# NVME.net
KiCad netlist of a schematic drawn in Altium Designer
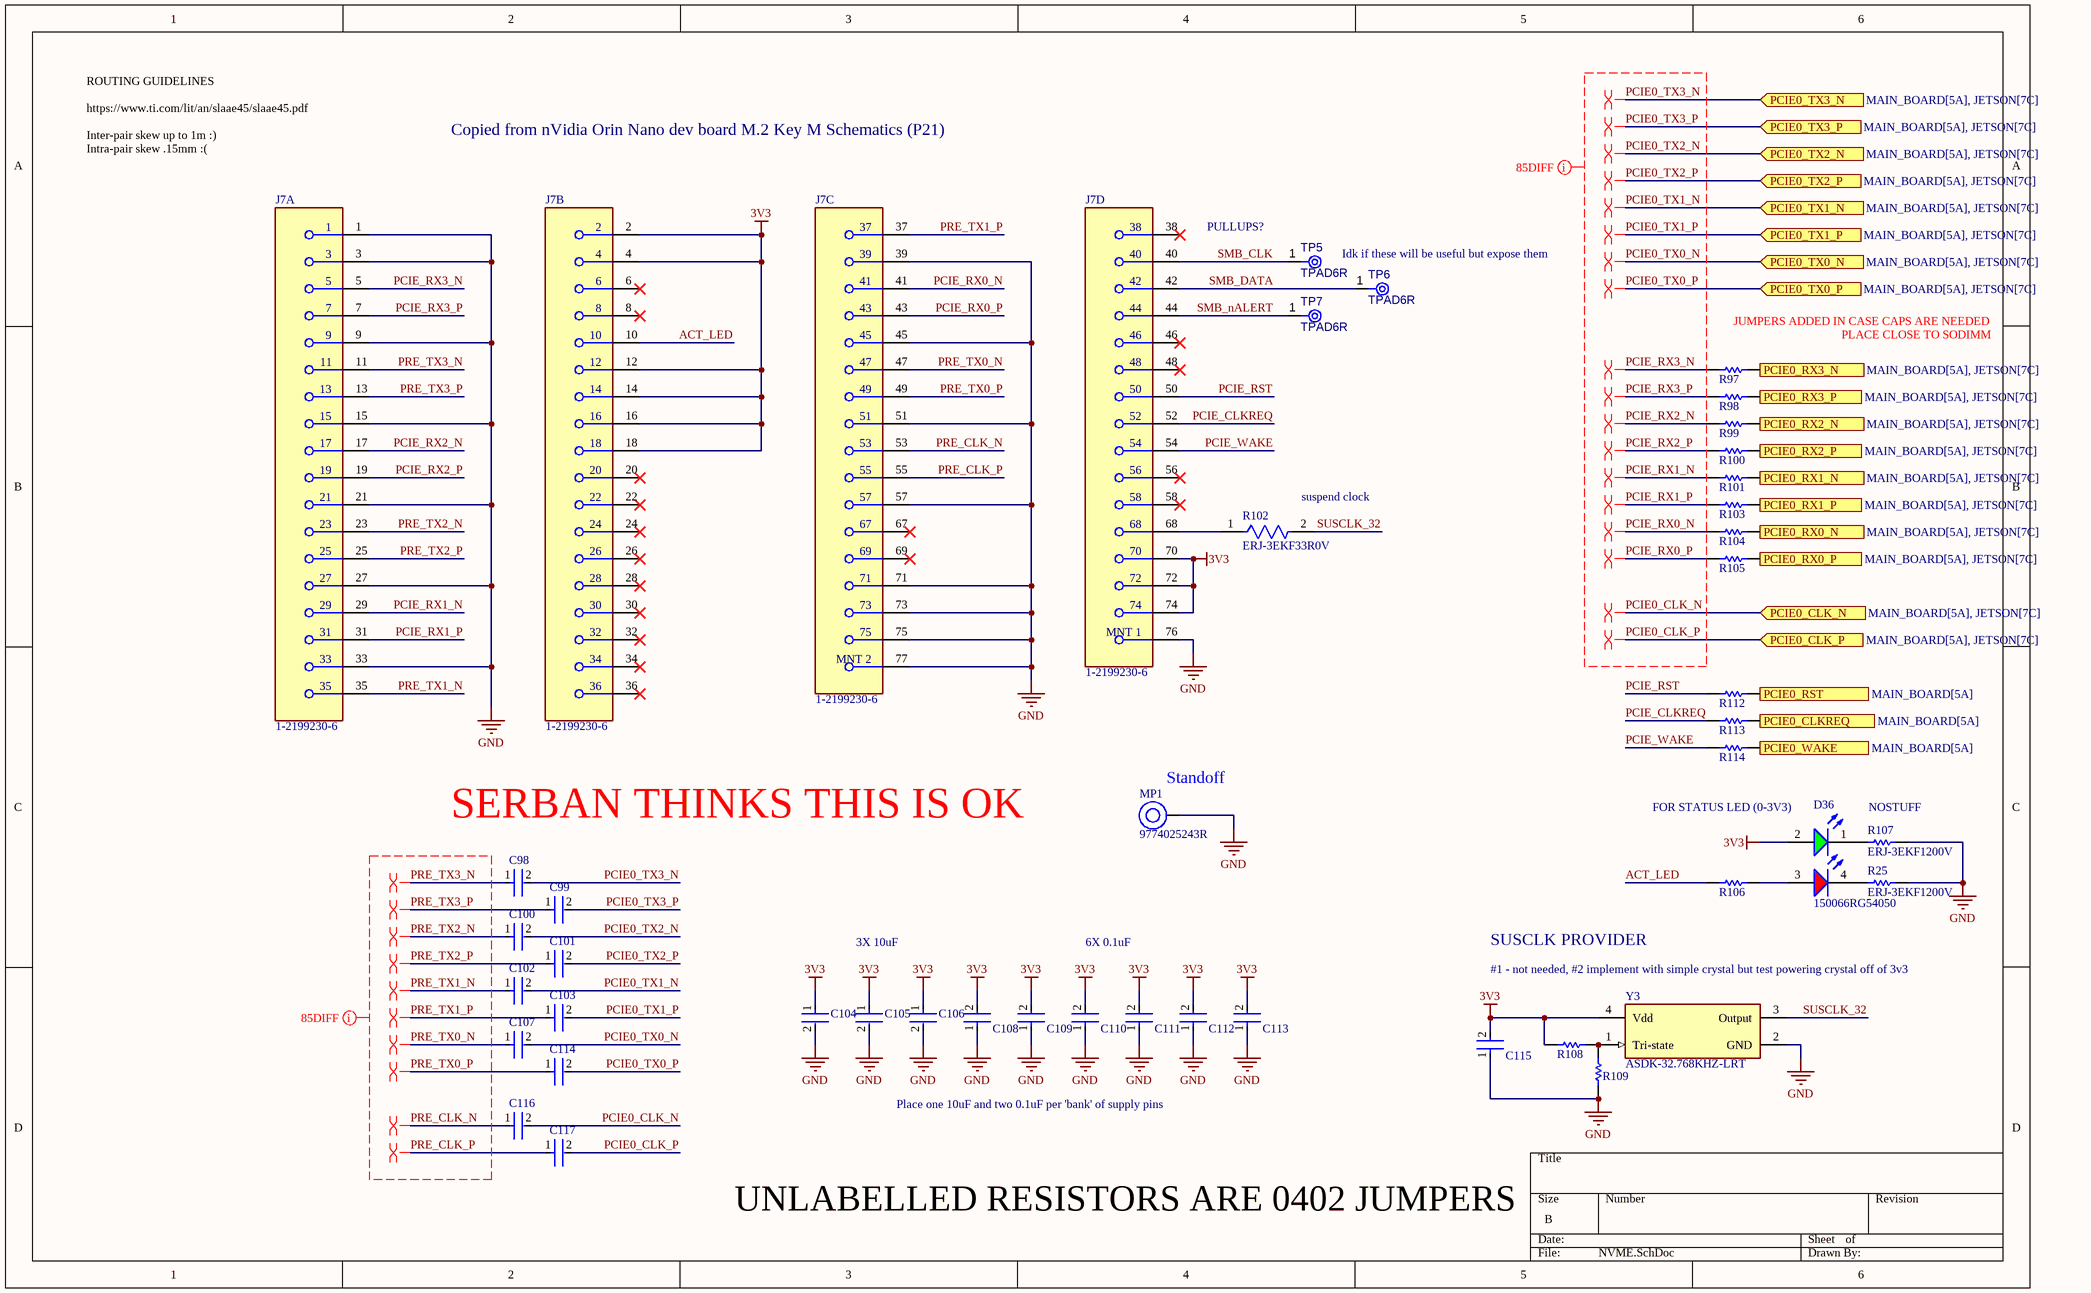
[diagram p0: NVME.SchDoc]

(export (version "E")
  (design (tool "Eeschema 10.0.6"))
  (components
    (comp (ref "C98")
      (value "C1005X7R1A224K050BB")
      (footprint "FP-C1005-050-0_05-IPC_C")
      (description "Multilayer Ceramic Capacitors 220nF ±10% 10V X7R SMD 0402")
      (fields (field (name "TOLERANCE") "10%"))
      (libsource (lib "Altium Content Vault") (part "b4654b650e69147ec39a6b967a45e02"))
    )
    (comp (ref "C99")
      (value "C1005X7R1A224K050BB")
      (footprint "FP-C1005-050-0_05-IPC_C")
      (description "Multilayer Ceramic Capacitors 220nF ±10% 10V X7R SMD 0402")
      (fields (field (name "TOLERANCE") "10%"))
      (libsource (lib "Altium Content Vault") (part "b4654b650e69147ec39a6b967a45e02"))
    )
    (comp (ref "C100")
      (value "C1005X7R1A224K050BB")
      (footprint "FP-C1005-050-0_05-IPC_C")
      (description "Multilayer Ceramic Capacitors 220nF ±10% 10V X7R SMD 0402")
      (fields (field (name "TOLERANCE") "10%"))
      (libsource (lib "Altium Content Vault") (part "b4654b650e69147ec39a6b967a45e02"))
    )
    (comp (ref "C101")
      (value "C1005X7R1A224K050BB")
      (footprint "FP-C1005-050-0_05-IPC_C")
      (description "Multilayer Ceramic Capacitors 220nF ±10% 10V X7R SMD 0402")
      (fields (field (name "TOLERANCE") "10%"))
      (libsource (lib "Altium Content Vault") (part "b4654b650e69147ec39a6b967a45e02"))
    )
    (comp (ref "C102")
      (value "C1005X7R1A224K050BB")
      (footprint "FP-C1005-050-0_05-IPC_C")
      (description "Multilayer Ceramic Capacitors 220nF ±10% 10V X7R SMD 0402")
      (fields (field (name "TOLERANCE") "10%"))
      (libsource (lib "Altium Content Vault") (part "b4654b650e69147ec39a6b967a45e02"))
    )
    (comp (ref "C103")
      (value "C1005X7R1A224K050BB")
      (footprint "FP-C1005-050-0_05-IPC_C")
      (description "Multilayer Ceramic Capacitors 220nF ±10% 10V X7R SMD 0402")
      (fields (field (name "TOLERANCE") "10%"))
      (libsource (lib "Altium Content Vault") (part "b4654b650e69147ec39a6b967a45e02"))
    )
    (comp (ref "C104")
      (value "GRM188R60J106ME47D")
      (footprint "FP-GRM188-0_1-e0_2_0_55-IPC_A")
      (description "Chip Multilayer Ceramic Capacitors for General Purpose, 0603, 10uF, X5R, 15%, 20%, 6.3V")
      (fields (field (name "VOLTAGE") "6.3V") (field (name "TOLERANCE") "20%"))
      (libsource (lib "Altium Content Vault") (part "02cd4be3c70576c341d710602a673aa"))
    )
    (comp (ref "C105")
      (value "GRM188R60J106ME47D")
      (footprint "FP-GRM188-0_1-e0_2_0_55-IPC_A")
      (description "Chip Multilayer Ceramic Capacitors for General Purpose, 0603, 10uF, X5R, 15%, 20%, 6.3V")
      (fields (field (name "VOLTAGE") "6.3V") (field (name "TOLERANCE") "20%"))
      (libsource (lib "Altium Content Vault") (part "02cd4be3c70576c341d710602a673aa"))
    )
    (comp (ref "C106")
      (value "GRM188R60J106ME47D")
      (footprint "FP-GRM188-0_1-e0_2_0_55-IPC_A")
      (description "Chip Multilayer Ceramic Capacitors for General Purpose, 0603, 10uF, X5R, 15%, 20%, 6.3V")
      (fields (field (name "VOLTAGE") "6.3V") (field (name "TOLERANCE") "20%"))
      (libsource (lib "Altium Content Vault") (part "02cd4be3c70576c341d710602a673aa"))
    )
    (comp (ref "C107")
      (value "C1005X7R1A224K050BB")
      (footprint "FP-C1005-050-0_05-IPC_C")
      (description "Multilayer Ceramic Capacitors 220nF ±10% 10V X7R SMD 0402")
      (fields (field (name "TOLERANCE") "10%"))
      (libsource (lib "Altium Content Vault") (part "b4654b650e69147ec39a6b967a45e02"))
    )
    (comp (ref "C108")
      (value "C1005X7R1H104K050BB")
      (footprint "FP-C1005-050-0_05-IPC_C")
      (description "Multilayer Ceramic Capacitors 100nF ±10% 50V X7R SMD 0402")
      (fields (field (name "VOLTAGE") "50V") (field (name "TOLERANCE") "10%"))
      (libsource (lib "Altium Content Vault") (part "b4654b650e69147ec39a6b967a45e02"))
    )
    (comp (ref "C109")
      (value "C1005X7R1H104K050BB")
      (footprint "FP-C1005-050-0_05-IPC_C")
      (description "Multilayer Ceramic Capacitors 100nF ±10% 50V X7R SMD 0402")
      (fields (field (name "VOLTAGE") "50V") (field (name "TOLERANCE") "10%"))
      (libsource (lib "Altium Content Vault") (part "b4654b650e69147ec39a6b967a45e02"))
    )
    (comp (ref "C110")
      (value "C1005X7R1H104K050BB")
      (footprint "FP-C1005-050-0_05-IPC_C")
      (description "Multilayer Ceramic Capacitors 100nF ±10% 50V X7R SMD 0402")
      (fields (field (name "VOLTAGE") "50V") (field (name "TOLERANCE") "10%"))
      (libsource (lib "Altium Content Vault") (part "b4654b650e69147ec39a6b967a45e02"))
    )
    (comp (ref "C111")
      (value "C1005X7R1H104K050BB")
      (footprint "FP-C1005-050-0_05-IPC_C")
      (description "Multilayer Ceramic Capacitors 100nF ±10% 50V X7R SMD 0402")
      (fields (field (name "VOLTAGE") "50V") (field (name "TOLERANCE") "10%"))
      (libsource (lib "Altium Content Vault") (part "b4654b650e69147ec39a6b967a45e02"))
    )
    (comp (ref "C112")
      (value "C1005X7R1H104K050BB")
      (footprint "FP-C1005-050-0_05-IPC_C")
      (description "Multilayer Ceramic Capacitors 100nF ±10% 50V X7R SMD 0402")
      (fields (field (name "VOLTAGE") "50V") (field (name "TOLERANCE") "10%"))
      (libsource (lib "Altium Content Vault") (part "b4654b650e69147ec39a6b967a45e02"))
    )
    (comp (ref "C113")
      (value "C1005X7R1H104K050BB")
      (footprint "FP-C1005-050-0_05-IPC_C")
      (description "Multilayer Ceramic Capacitors 100nF ±10% 50V X7R SMD 0402")
      (fields (field (name "VOLTAGE") "50V") (field (name "TOLERANCE") "10%"))
      (libsource (lib "Altium Content Vault") (part "b4654b650e69147ec39a6b967a45e02"))
    )
    (comp (ref "C114")
      (value "C1005X7R1A224K050BB")
      (footprint "FP-C1005-050-0_05-IPC_C")
      (description "Multilayer Ceramic Capacitors 220nF ±10% 10V X7R SMD 0402")
      (fields (field (name "TOLERANCE") "10%"))
      (libsource (lib "Altium Content Vault") (part "b4654b650e69147ec39a6b967a45e02"))
    )
    (comp (ref "C115")
      (value "C1005X7R1H104K050BB")
      (footprint "FP-C1005-050-0_05-IPC_C")
      (description "Multilayer Ceramic Capacitors 100nF ±10% 50V X7R SMD 0402")
      (fields (field (name "VOLTAGE") "50V") (field (name "TOLERANCE") "10%"))
      (libsource (lib "Altium Content Vault") (part "b4654b650e69147ec39a6b967a45e02"))
    )
    (comp (ref "C116")
      (value "C1005X7R1A224K050BB")
      (footprint "FP-C1005-050-0_05-IPC_C")
      (description "Multilayer Ceramic Capacitors 220nF ±10% 10V X7R SMD 0402")
      (fields (field (name "TOLERANCE") "10%"))
      (libsource (lib "Altium Content Vault") (part "b4654b650e69147ec39a6b967a45e02"))
    )
    (comp (ref "C117")
      (value "C1005X7R1A224K050BB")
      (footprint "FP-C1005-050-0_05-IPC_C")
      (description "Multilayer Ceramic Capacitors 220nF ±10% 10V X7R SMD 0402")
      (fields (field (name "TOLERANCE") "10%"))
      (libsource (lib "Altium Content Vault") (part "b4654b650e69147ec39a6b967a45e02"))
    )
    (comp (ref "D36")
      (value "150066RG54050")
      (footprint "WL-SBCD_0606")
      (description "Led, Red/Grn, 180Mcd/230Mcd, 624Nm/525Nm Rohs Compliant: Yes")
      (libsource (lib "uORocketry Hardware") (part "WL-SBCD_0606_Red & Green"))
    )
    (comp (ref "J7")
      (value "1-2199230-6")
      (footprint "FP-1-2199230-6-MFG")
      (description "CONN EDGE DUAL FMALE 67POS 0.020")
      (fields
        (field (name "MANUFACTURER") "TE")
        (field (name "OCTOPART") "https://octopart.com/1-2199230-6-te+connectivity-34969376")
      )
      (libsource (lib "Altium Content Vault") (part "bdc5cd39fb5e3adfc3cf7d042564072"))
    )
    (comp (ref "MP1")
      (value "9774025243R")
      (footprint "9774025243")
      (description "9774025243R Spacer Material: Steel, Tin-Plated Mounting: SMT Series: WA-SMST Thread D: M2")
      (libsource (lib "Altium Content Vault") (part "Spacer"))
    )
    (comp (ref "R25")
      (value "ERJ-3EKF1200V")
      (footprint "RESC1609X55X30ML15T15")
      (description "Chip Resistor, 120 Ohm, +/- 1%, 0.1 W, -55 to 155 degC, 0603 (1608 Metric), RoHS, Tape and Reel")
      (fields (field (name "TOLERANCE") "1%") (field (name "MANUFACTURER") "Panasonic"))
      (libsource (lib "Altium Content Vault") (part "RES-2"))
    )
    (comp (ref "R97")
      (value "0402 JUMPER 0 OHM")
      (footprint "RESC1005X40X25NL05T05")
      (description "READ THE NAME")
      (libsource (lib "uORocketry Hardware") (part "RES"))
    )
    (comp (ref "R98")
      (value "0402 JUMPER 0 OHM")
      (footprint "RESC1005X40X25NL05T05")
      (description "READ THE NAME")
      (libsource (lib "uORocketry Hardware") (part "RES"))
    )
    (comp (ref "R99")
      (value "0402 JUMPER 0 OHM")
      (footprint "RESC1005X40X25NL05T05")
      (description "READ THE NAME")
      (libsource (lib "uORocketry Hardware") (part "RES"))
    )
    (comp (ref "R100")
      (value "0402 JUMPER 0 OHM")
      (footprint "RESC1005X40X25NL05T05")
      (description "READ THE NAME")
      (libsource (lib "uORocketry Hardware") (part "RES"))
    )
    (comp (ref "R101")
      (value "0402 JUMPER 0 OHM")
      (footprint "RESC1005X40X25NL05T05")
      (description "READ THE NAME")
      (libsource (lib "uORocketry Hardware") (part "RES"))
    )
    (comp (ref "R102")
      (value "ERJ-3EKF33R0V")
      (footprint "FP-ERJ3EK-MFG")
      (description "RES SMD 33 OHM 1% 1/10W 0603")
      (fields (field (name "TOLERANCE") "1%"))
      (libsource (lib "Altium Content Vault") (part "1029c3af85768c4190bb7ad29bc67b5"))
    )
    (comp (ref "R103")
      (value "0402 JUMPER 0 OHM")
      (footprint "RESC1005X40X25NL05T05")
      (description "READ THE NAME")
      (libsource (lib "uORocketry Hardware") (part "RES"))
    )
    (comp (ref "R104")
      (value "0402 JUMPER 0 OHM")
      (footprint "RESC1005X40X25NL05T05")
      (description "READ THE NAME")
      (libsource (lib "uORocketry Hardware") (part "RES"))
    )
    (comp (ref "R105")
      (value "0402 JUMPER 0 OHM")
      (footprint "RESC1005X40X25NL05T05")
      (description "READ THE NAME")
      (libsource (lib "uORocketry Hardware") (part "RES"))
    )
    (comp (ref "R106")
      (value "0402 JUMPER 0 OHM")
      (footprint "RESC1005X40X25NL05T05")
      (description "READ THE NAME")
      (libsource (lib "uORocketry Hardware") (part "RES"))
    )
    (comp (ref "R107")
      (value "ERJ-3EKF1200V")
      (footprint "RESC1609X55X30ML15T15")
      (description "Chip Resistor, 120 Ohm, +/- 1%, 0.1 W, -55 to 155 degC, 0603 (1608 Metric), RoHS, Tape and Reel")
      (fields (field (name "TOLERANCE") "1%") (field (name "MANUFACTURER") "Panasonic"))
      (libsource (lib "Altium Content Vault") (part "RES-2"))
    )
    (comp (ref "R108")
      (value "0402 JUMPER 0 OHM")
      (footprint "RESC1005X40X25NL05T05")
      (description "READ THE NAME")
      (libsource (lib "uORocketry Hardware") (part "RES"))
    )
    (comp (ref "R109")
      (value "0402 JUMPER 0 OHM")
      (footprint "RESC1005X40X25NL05T05")
      (description "READ THE NAME")
      (libsource (lib "uORocketry Hardware") (part "RES"))
    )
    (comp (ref "R112")
      (value "0402 JUMPER 0 OHM")
      (footprint "RESC1005X40X25NL05T05")
      (description "READ THE NAME")
      (libsource (lib "uORocketry Hardware") (part "RES"))
    )
    (comp (ref "R113")
      (value "0402 JUMPER 0 OHM")
      (footprint "RESC1005X40X25NL05T05")
      (description "READ THE NAME")
      (libsource (lib "uORocketry Hardware") (part "RES"))
    )
    (comp (ref "R114")
      (value "0402 JUMPER 0 OHM")
      (footprint "RESC1005X40X25NL05T05")
      (description "READ THE NAME")
      (libsource (lib "uORocketry Hardware") (part "RES"))
    )
    (comp (ref "TP5")
      (value "TPAD6R")
      (footprint "TP06R")
      (description "0.6mm round")
      (libsource (lib "uORocketry Hardware") (part "CMP-001-0001-4"))
    )
    (comp (ref "TP6")
      (value "TPAD6R")
      (footprint "TP06R")
      (description "0.6mm round")
      (libsource (lib "uORocketry Hardware") (part "CMP-001-0001-4"))
    )
    (comp (ref "TP7")
      (value "TPAD6R")
      (footprint "TP06R")
      (description "0.6mm round")
      (libsource (lib "uORocketry Hardware") (part "CMP-001-0001-4"))
    )
    (comp (ref "Y3")
      (value "ASDK-32.768KHZ-LRT")
      (footprint "FP-ASDK-MFG")
      (description "XTAL OSC XO 32.7680KHZ CMOS SMD")
      (libsource (lib "Altium Content Vault") (part "a7425352bb6ebc83bfd0f12a23808e7"))
    )
  )
  (nets
    (net (code "1") (name "/ACT_LED") (class "Default")
      (node (ref "J7") (pin "10") (pinfunction "10_10") (pintype "passive"))
      (node (ref "R106") (pin "1") (pinfunction "1_1") (pintype "passive"))
    )
    (net (code "2") (name "/PCIE0_CLKREQ") (class "Default")
      (node (ref "R113") (pin "2") (pinfunction "2_2") (pintype "passive"))
    )
    (net (code "3") (name "/PCIE0_CLK_N") (class "Default")
      (node (ref "C116") (pin "2") (pinfunction "2_2") (pintype "passive"))
    )
    (net (code "4") (name "/PCIE0_CLK_P") (class "Default")
      (node (ref "C117") (pin "2") (pinfunction "2_2") (pintype "passive"))
    )
    (net (code "5") (name "/PCIE0_RST") (class "Default")
      (node (ref "R112") (pin "2") (pinfunction "2_2") (pintype "passive"))
    )
    (net (code "6") (name "/PCIE0_RX0_N") (class "Default")
      (node (ref "R104") (pin "2") (pinfunction "2_2") (pintype "passive"))
    )
    (net (code "7") (name "/PCIE0_RX0_P") (class "Default")
      (node (ref "R105") (pin "2") (pinfunction "2_2") (pintype "passive"))
    )
    (net (code "8") (name "/PCIE0_RX1_N") (class "Default")
      (node (ref "R101") (pin "2") (pinfunction "2_2") (pintype "passive"))
    )
    (net (code "9") (name "/PCIE0_RX1_P") (class "Default")
      (node (ref "R103") (pin "2") (pinfunction "2_2") (pintype "passive"))
    )
    (net (code "10") (name "/PCIE0_RX2_N") (class "Default")
      (node (ref "R99") (pin "2") (pinfunction "2_2") (pintype "passive"))
    )
    (net (code "11") (name "/PCIE0_RX2_P") (class "Default")
      (node (ref "R100") (pin "2") (pinfunction "2_2") (pintype "passive"))
    )
    (net (code "12") (name "/PCIE0_RX3_N") (class "Default")
      (node (ref "R97") (pin "2") (pinfunction "2_2") (pintype "passive"))
    )
    (net (code "13") (name "/PCIE0_RX3_P") (class "Default")
      (node (ref "R98") (pin "2") (pinfunction "2_2") (pintype "passive"))
    )
    (net (code "14") (name "/PCIE0_TX0_N") (class "Default")
      (node (ref "C107") (pin "2") (pinfunction "2_2") (pintype "passive"))
    )
    (net (code "15") (name "/PCIE0_TX0_P") (class "Default")
      (node (ref "C114") (pin "2") (pinfunction "2_2") (pintype "passive"))
    )
    (net (code "16") (name "/PCIE0_TX1_N") (class "Default")
      (node (ref "C102") (pin "2") (pinfunction "2_2") (pintype "passive"))
    )
    (net (code "17") (name "/PCIE0_TX1_P") (class "Default")
      (node (ref "C103") (pin "2") (pinfunction "2_2") (pintype "passive"))
    )
    (net (code "18") (name "/PCIE0_TX2_N") (class "Default")
      (node (ref "C100") (pin "2") (pinfunction "2_2") (pintype "passive"))
    )
    (net (code "19") (name "/PCIE0_TX2_P") (class "Default")
      (node (ref "C101") (pin "2") (pinfunction "2_2") (pintype "passive"))
    )
    (net (code "20") (name "/PCIE0_TX3_N") (class "Default")
      (node (ref "C98") (pin "2") (pinfunction "2_2") (pintype "passive"))
    )
    (net (code "21") (name "/PCIE0_TX3_P") (class "Default")
      (node (ref "C99") (pin "2") (pinfunction "2_2") (pintype "passive"))
    )
    (net (code "22") (name "/PCIE0_WAKE") (class "Default")
      (node (ref "R114") (pin "2") (pinfunction "2_2") (pintype "passive"))
    )
    (net (code "23") (name "/PCIE_CLKREQ") (class "Default")
      (node (ref "J7") (pin "52") (pinfunction "52_52") (pintype "passive"))
      (node (ref "R113") (pin "1") (pinfunction "1_1") (pintype "passive"))
    )
    (net (code "24") (name "/PCIE_RST") (class "Default")
      (node (ref "J7") (pin "50") (pinfunction "50_50") (pintype "passive"))
      (node (ref "R112") (pin "1") (pinfunction "1_1") (pintype "passive"))
    )
    (net (code "25") (name "/PCIE_RX0_N") (class "Default")
      (node (ref "J7") (pin "41") (pinfunction "41_41") (pintype "passive"))
      (node (ref "R104") (pin "1") (pinfunction "1_1") (pintype "passive"))
    )
    (net (code "26") (name "/PCIE_RX0_P") (class "Default")
      (node (ref "J7") (pin "43") (pinfunction "43_43") (pintype "passive"))
      (node (ref "R105") (pin "1") (pinfunction "1_1") (pintype "passive"))
    )
    (net (code "27") (name "/PCIE_RX1_N") (class "Default")
      (node (ref "J7") (pin "29") (pinfunction "29_29") (pintype "passive"))
      (node (ref "R101") (pin "1") (pinfunction "1_1") (pintype "passive"))
    )
    (net (code "28") (name "/PCIE_RX1_P") (class "Default")
      (node (ref "J7") (pin "31") (pinfunction "31_31") (pintype "passive"))
      (node (ref "R103") (pin "1") (pinfunction "1_1") (pintype "passive"))
    )
    (net (code "29") (name "/PCIE_RX2_N") (class "Default")
      (node (ref "J7") (pin "17") (pinfunction "17_17") (pintype "passive"))
      (node (ref "R99") (pin "1") (pinfunction "1_1") (pintype "passive"))
    )
    (net (code "30") (name "/PCIE_RX2_P") (class "Default")
      (node (ref "J7") (pin "19") (pinfunction "19_19") (pintype "passive"))
      (node (ref "R100") (pin "1") (pinfunction "1_1") (pintype "passive"))
    )
    (net (code "31") (name "/PCIE_RX3_N") (class "Default")
      (node (ref "J7") (pin "5") (pinfunction "5_5") (pintype "passive"))
      (node (ref "R97") (pin "1") (pinfunction "1_1") (pintype "passive"))
    )
    (net (code "32") (name "/PCIE_RX3_P") (class "Default")
      (node (ref "J7") (pin "7") (pinfunction "7_7") (pintype "passive"))
      (node (ref "R98") (pin "1") (pinfunction "1_1") (pintype "passive"))
    )
    (net (code "33") (name "/PCIE_WAKE") (class "Default")
      (node (ref "J7") (pin "54") (pinfunction "54_54") (pintype "passive"))
      (node (ref "R114") (pin "1") (pinfunction "1_1") (pintype "passive"))
    )
    (net (code "34") (name "/PRE_CLK_N") (class "Default")
      (node (ref "C116") (pin "1") (pinfunction "1_1") (pintype "passive"))
      (node (ref "J7") (pin "53") (pinfunction "53_53") (pintype "passive"))
    )
    (net (code "35") (name "/PRE_CLK_P") (class "Default")
      (node (ref "C117") (pin "1") (pinfunction "1_1") (pintype "passive"))
      (node (ref "J7") (pin "55") (pinfunction "55_55") (pintype "passive"))
    )
    (net (code "36") (name "/PRE_TX0_N") (class "Default")
      (node (ref "C107") (pin "1") (pinfunction "1_1") (pintype "passive"))
      (node (ref "J7") (pin "47") (pinfunction "47_47") (pintype "passive"))
    )
    (net (code "37") (name "/PRE_TX0_P") (class "Default")
      (node (ref "C114") (pin "1") (pinfunction "1_1") (pintype "passive"))
      (node (ref "J7") (pin "49") (pinfunction "49_49") (pintype "passive"))
    )
    (net (code "38") (name "/PRE_TX1_N") (class "Default")
      (node (ref "C102") (pin "1") (pinfunction "1_1") (pintype "passive"))
      (node (ref "J7") (pin "35") (pinfunction "35_35") (pintype "passive"))
    )
    (net (code "39") (name "/PRE_TX1_P") (class "Default")
      (node (ref "C103") (pin "1") (pinfunction "1_1") (pintype "passive"))
      (node (ref "J7") (pin "37") (pinfunction "37_37") (pintype "passive"))
    )
    (net (code "40") (name "/PRE_TX2_N") (class "Default")
      (node (ref "C100") (pin "1") (pinfunction "1_1") (pintype "passive"))
      (node (ref "J7") (pin "23") (pinfunction "23_23") (pintype "passive"))
    )
    (net (code "41") (name "/PRE_TX2_P") (class "Default")
      (node (ref "C101") (pin "1") (pinfunction "1_1") (pintype "passive"))
      (node (ref "J7") (pin "25") (pinfunction "25_25") (pintype "passive"))
    )
    (net (code "42") (name "/PRE_TX3_N") (class "Default")
      (node (ref "C98") (pin "1") (pinfunction "1_1") (pintype "passive"))
      (node (ref "J7") (pin "11") (pinfunction "11_11") (pintype "passive"))
    )
    (net (code "43") (name "/PRE_TX3_P") (class "Default")
      (node (ref "C99") (pin "1") (pinfunction "1_1") (pintype "passive"))
      (node (ref "J7") (pin "13") (pinfunction "13_13") (pintype "passive"))
    )
    (net (code "44") (name "/SMB_CLK") (class "Default")
      (node (ref "J7") (pin "40") (pinfunction "40_40") (pintype "passive"))
      (node (ref "TP5") (pin "1") (pinfunction "TP_1") (pintype "passive"))
    )
    (net (code "45") (name "/SMB_DATA") (class "Default")
      (node (ref "J7") (pin "42") (pinfunction "42_42") (pintype "passive"))
      (node (ref "TP6") (pin "1") (pinfunction "TP_1") (pintype "passive"))
    )
    (net (code "46") (name "/SMB_nALERT") (class "Default")
      (node (ref "J7") (pin "44") (pinfunction "44_44") (pintype "passive"))
      (node (ref "TP7") (pin "1") (pinfunction "TP_1") (pintype "passive"))
    )
    (net (code "47") (name "/SUSCLK_32") (class "Default")
      (node (ref "R102") (pin "2") (pinfunction "2_2") (pintype "passive"))
      (node (ref "Y3") (pin "3") (pinfunction "Output_3") (pintype "tri_state"))
    )
    (net (code "48") (name "3V3") (class "Default")
      (node (ref "C104") (pin "1") (pinfunction "1_1") (pintype "passive"))
      (node (ref "C105") (pin "1") (pinfunction "1_1") (pintype "passive"))
      (node (ref "C106") (pin "1") (pinfunction "1_1") (pintype "passive"))
      (node (ref "C108") (pin "2") (pinfunction "2_2") (pintype "passive"))
      (node (ref "C109") (pin "2") (pinfunction "2_2") (pintype "passive"))
      (node (ref "C110") (pin "2") (pinfunction "2_2") (pintype "passive"))
      (node (ref "C111") (pin "2") (pinfunction "2_2") (pintype "passive"))
      (node (ref "C112") (pin "2") (pinfunction "2_2") (pintype "passive"))
      (node (ref "C113") (pin "2") (pinfunction "2_2") (pintype "passive"))
      (node (ref "C115") (pin "2") (pinfunction "2_2") (pintype "passive"))
      (node (ref "D36") (pin "2") (pinfunction "A_2") (pintype "passive"))
      (node (ref "J7") (pin "12") (pinfunction "12_12") (pintype "passive"))
      (node (ref "J7") (pin "14") (pinfunction "14_14") (pintype "passive"))
      (node (ref "J7") (pin "16") (pinfunction "16_16") (pintype "passive"))
      (node (ref "J7") (pin "18") (pinfunction "18_18") (pintype "passive"))
      (node (ref "J7") (pin "2") (pinfunction "2_2") (pintype "passive"))
      (node (ref "J7") (pin "4") (pinfunction "4_4") (pintype "passive"))
      (node (ref "J7") (pin "70") (pinfunction "70_70") (pintype "passive"))
      (node (ref "J7") (pin "72") (pinfunction "72_72") (pintype "passive"))
      (node (ref "J7") (pin "74") (pinfunction "74_74") (pintype "passive"))
      (node (ref "R108") (pin "1") (pinfunction "1_1") (pintype "passive"))
      (node (ref "Y3") (pin "4") (pinfunction "Vdd_4") (pintype "power_in"))
    )
    (net (code "49") (name "GND") (class "Default")
      (node (ref "C104") (pin "2") (pinfunction "2_2") (pintype "passive"))
      (node (ref "C105") (pin "2") (pinfunction "2_2") (pintype "passive"))
      (node (ref "C106") (pin "2") (pinfunction "2_2") (pintype "passive"))
      (node (ref "C108") (pin "1") (pinfunction "1_1") (pintype "passive"))
      (node (ref "C109") (pin "1") (pinfunction "1_1") (pintype "passive"))
      (node (ref "C110") (pin "1") (pinfunction "1_1") (pintype "passive"))
      (node (ref "C111") (pin "1") (pinfunction "1_1") (pintype "passive"))
      (node (ref "C112") (pin "1") (pinfunction "1_1") (pintype "passive"))
      (node (ref "C113") (pin "1") (pinfunction "1_1") (pintype "passive"))
      (node (ref "C115") (pin "1") (pinfunction "1_1") (pintype "passive"))
      (node (ref "J7") (pin "1") (pinfunction "1_1") (pintype "passive"))
      (node (ref "J7") (pin "15") (pinfunction "15_15") (pintype "passive"))
      (node (ref "J7") (pin "21") (pinfunction "21_21") (pintype "passive"))
      (node (ref "J7") (pin "27") (pinfunction "27_27") (pintype "passive"))
      (node (ref "J7") (pin "3") (pinfunction "3_3") (pintype "passive"))
      (node (ref "J7") (pin "33") (pinfunction "33_33") (pintype "passive"))
      (node (ref "J7") (pin "39") (pinfunction "39_39") (pintype "passive"))
      (node (ref "J7") (pin "45") (pinfunction "45_45") (pintype "passive"))
      (node (ref "J7") (pin "51") (pinfunction "51_51") (pintype "passive"))
      (node (ref "J7") (pin "57") (pinfunction "57_57") (pintype "passive"))
      (node (ref "J7") (pin "71") (pinfunction "71_71") (pintype "passive"))
      (node (ref "J7") (pin "73") (pinfunction "73_73") (pintype "passive"))
      (node (ref "J7") (pin "75") (pinfunction "75_75") (pintype "passive"))
      (node (ref "J7") (pin "76") (pinfunction "MNT_1_76") (pintype "passive"))
      (node (ref "J7") (pin "77") (pinfunction "MNT_2_77") (pintype "passive"))
      (node (ref "J7") (pin "9") (pinfunction "9_9") (pintype "passive"))
      (node (ref "MP1") (pin "1") (pinfunction "1_1") (pintype "passive"))
      (node (ref "R107") (pin "1") (pinfunction "1_1") (pintype "passive"))
      (node (ref "R109") (pin "1") (pinfunction "1_1") (pintype "passive"))
      (node (ref "R25") (pin "1") (pinfunction "1_1") (pintype "passive"))
      (node (ref "Y3") (pin "2") (pinfunction "GND_2") (pintype "power_in"))
    )
    (net (code "50") (name "Net-(D36-A-Pad3)") (class "Default")
      (node (ref "D36") (pin "3") (pinfunction "A_3") (pintype "passive"))
      (node (ref "R106") (pin "2") (pinfunction "2_2") (pintype "passive"))
    )
    (net (code "51") (name "Net-(D36-K-Pad1)") (class "Default")
      (node (ref "D36") (pin "1") (pinfunction "K_1") (pintype "passive"))
      (node (ref "R107") (pin "2") (pinfunction "2_2") (pintype "passive"))
    )
    (net (code "52") (name "Net-(D36-K-Pad4)") (class "Default")
      (node (ref "D36") (pin "4") (pinfunction "K_4") (pintype "passive"))
      (node (ref "R25") (pin "2") (pinfunction "2_2") (pintype "passive"))
    )
    (net (code "53") (name "Net-(J7-Pad68)") (class "Default")
      (node (ref "J7") (pin "68") (pinfunction "68_68") (pintype "passive"))
      (node (ref "R102") (pin "1") (pinfunction "1_1") (pintype "passive"))
    )
    (net (code "54") (name "Net-(Y3-Tri-state)") (class "Default")
      (node (ref "R108") (pin "2") (pinfunction "2_2") (pintype "passive"))
      (node (ref "R109") (pin "2") (pinfunction "2_2") (pintype "passive"))
      (node (ref "Y3") (pin "1") (pinfunction "Tri-state_1") (pintype "input"))
    )
    (net (code "55") (name "unconnected-(J7-Pad6)") (class "Default")
      (node (ref "J7") (pin "6") (pinfunction "6_6") (pintype "passive+no_connect"))
    )
    (net (code "56") (name "unconnected-(J7-Pad8)") (class "Default")
      (node (ref "J7") (pin "8") (pinfunction "8_8") (pintype "passive+no_connect"))
    )
    (net (code "57") (name "unconnected-(J7-Pad20)") (class "Default")
      (node (ref "J7") (pin "20") (pinfunction "20_20") (pintype "passive+no_connect"))
    )
    (net (code "58") (name "unconnected-(J7-Pad22)") (class "Default")
      (node (ref "J7") (pin "22") (pinfunction "22_22") (pintype "passive+no_connect"))
    )
    (net (code "59") (name "unconnected-(J7-Pad24)") (class "Default")
      (node (ref "J7") (pin "24") (pinfunction "24_24") (pintype "passive+no_connect"))
    )
    (net (code "60") (name "unconnected-(J7-Pad26)") (class "Default")
      (node (ref "J7") (pin "26") (pinfunction "26_26") (pintype "passive+no_connect"))
    )
    (net (code "61") (name "unconnected-(J7-Pad28)") (class "Default")
      (node (ref "J7") (pin "28") (pinfunction "28_28") (pintype "passive+no_connect"))
    )
    (net (code "62") (name "unconnected-(J7-Pad30)") (class "Default")
      (node (ref "J7") (pin "30") (pinfunction "30_30") (pintype "passive+no_connect"))
    )
    (net (code "63") (name "unconnected-(J7-Pad32)") (class "Default")
      (node (ref "J7") (pin "32") (pinfunction "32_32") (pintype "passive+no_connect"))
    )
    (net (code "64") (name "unconnected-(J7-Pad34)") (class "Default")
      (node (ref "J7") (pin "34") (pinfunction "34_34") (pintype "passive+no_connect"))
    )
    (net (code "65") (name "unconnected-(J7-Pad36)") (class "Default")
      (node (ref "J7") (pin "36") (pinfunction "36_36") (pintype "passive+no_connect"))
    )
    (net (code "66") (name "unconnected-(J7-Pad38)") (class "Default")
      (node (ref "J7") (pin "38") (pinfunction "38_38") (pintype "passive+no_connect"))
    )
    (net (code "67") (name "unconnected-(J7-Pad46)") (class "Default")
      (node (ref "J7") (pin "46") (pinfunction "46_46") (pintype "passive+no_connect"))
    )
    (net (code "68") (name "unconnected-(J7-Pad48)") (class "Default")
      (node (ref "J7") (pin "48") (pinfunction "48_48") (pintype "passive+no_connect"))
    )
    (net (code "69") (name "unconnected-(J7-Pad56)") (class "Default")
      (node (ref "J7") (pin "56") (pinfunction "56_56") (pintype "passive+no_connect"))
    )
    (net (code "70") (name "unconnected-(J7-Pad58)") (class "Default")
      (node (ref "J7") (pin "58") (pinfunction "58_58") (pintype "passive+no_connect"))
    )
    (net (code "71") (name "unconnected-(J7-Pad67)") (class "Default")
      (node (ref "J7") (pin "67") (pinfunction "67_67") (pintype "passive+no_connect"))
    )
    (net (code "72") (name "unconnected-(J7-Pad69)") (class "Default")
      (node (ref "J7") (pin "69") (pinfunction "69_69") (pintype "passive+no_connect"))
    )
  )
)
